# 2.net
KiCad netlist of a schematic drawn in Altium Designer
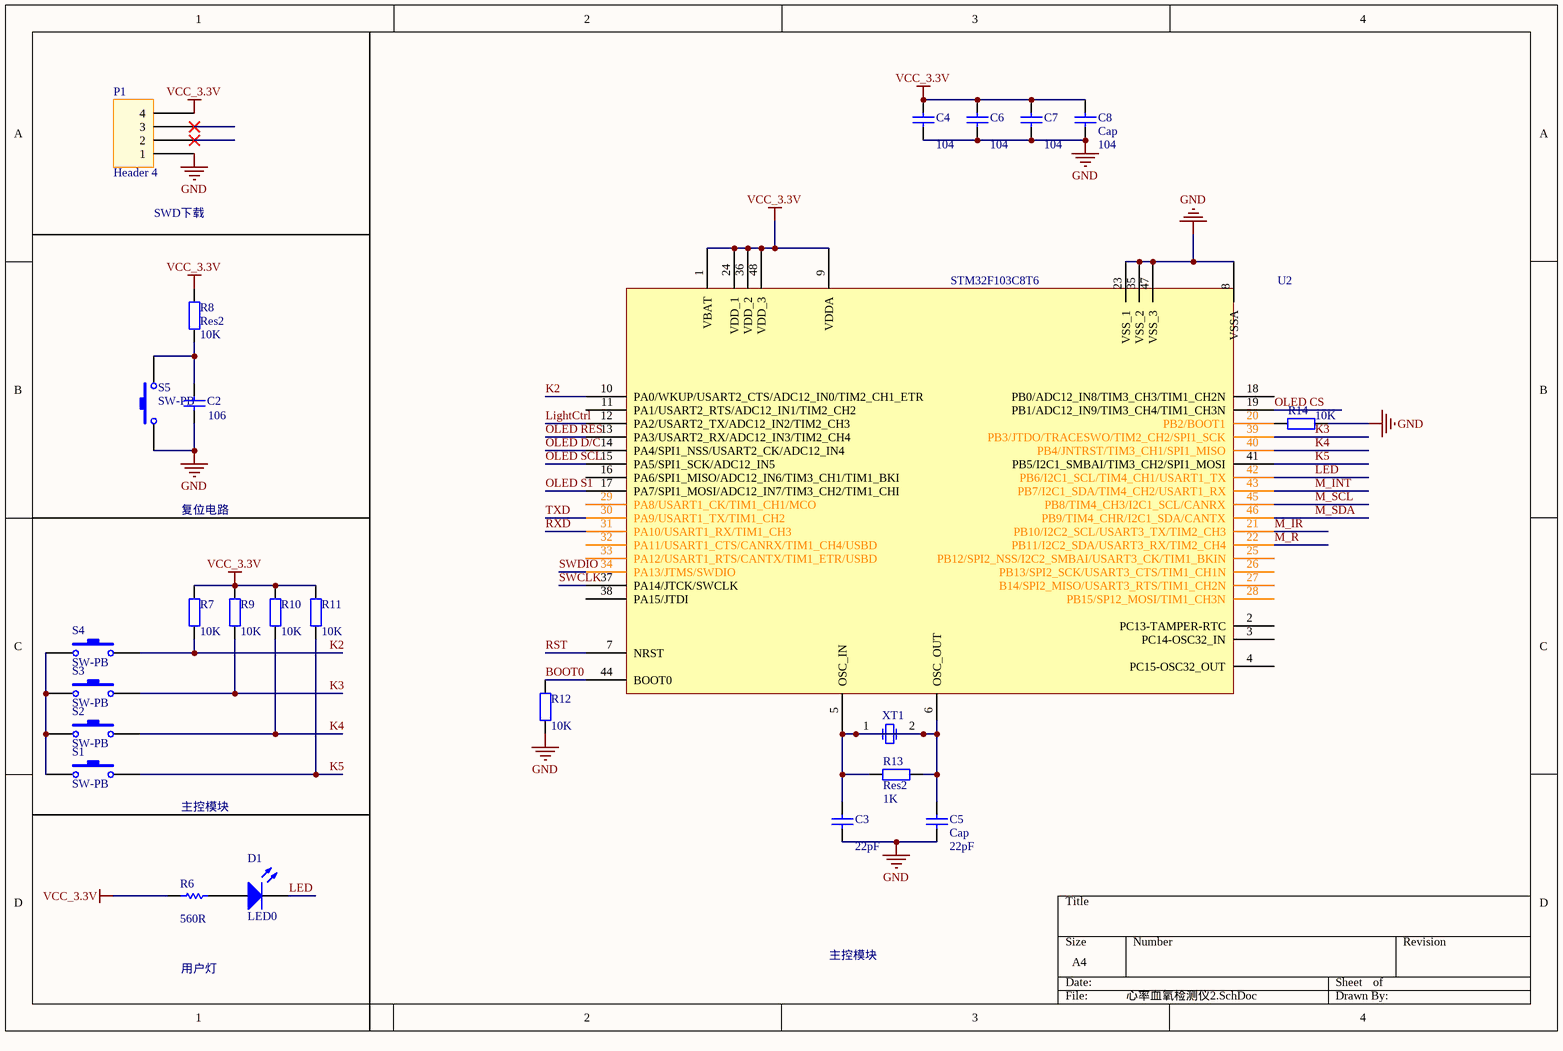
[diagram p0: 心率血氧检测仪2.SchDoc]

(export (version "E")
  (design (tool "Eeschema 10.0.6"))
  (components
    (comp (ref "C2")
      (value "106")
      (footprint "0805C")
      (description "Capacitor")
      (fields (field (name "Comment") "Cap") (field (name "PUBLISHER") "Altium Limited"))
      (libsource (lib "Miscellaneous Devices") (part "Cap"))
    )
    (comp (ref "C3")
      (value "22pF")
      (footprint "0805C")
      (description "Capacitor")
      (fields (field (name "Comment") "Cap") (field (name "PUBLISHER") "Altium Limited"))
      (libsource (lib "Miscellaneous Devices") (part "Cap"))
    )
    (comp (ref "C4")
      (value "104")
      (footprint "0805C")
      (description "Capacitor")
      (fields (field (name "Comment") "Cap") (field (name "PUBLISHER") "Altium Limited"))
      (libsource (lib "Miscellaneous Devices") (part "Cap"))
    )
    (comp (ref "C5")
      (value "Cap")
      (footprint "0805C")
      (description "Capacitor")
      (fields (field (name "ALTIUM_VALUE") "22pF") (field (name "PUBLISHER") "Altium Limited"))
      (libsource (lib "Miscellaneous Devices") (part "Cap"))
    )
    (comp (ref "C6")
      (value "104")
      (footprint "0805C")
      (description "Capacitor")
      (fields (field (name "Comment") "Cap") (field (name "PUBLISHER") "Altium Limited"))
      (libsource (lib "Miscellaneous Devices") (part "Cap"))
    )
    (comp (ref "C7")
      (value "104")
      (footprint "0805C")
      (description "Capacitor")
      (fields (field (name "Comment") "Cap") (field (name "PUBLISHER") "Altium Limited"))
      (libsource (lib "Miscellaneous Devices") (part "Cap"))
    )
    (comp (ref "C8")
      (value "Cap")
      (footprint "0805C")
      (description "Capacitor")
      (fields (field (name "ALTIUM_VALUE") "104") (field (name "PUBLISHER") "Altium Limited"))
      (libsource (lib "Miscellaneous Devices") (part "Cap"))
    )
    (comp (ref "D1")
      (value "LED0")
      (footprint "LED_0805")
      (description "Typical INFRARED GaAs LED")
      (fields (field (name "PUBLISHER") "Altium Limited"))
      (libsource (lib "Miscellaneous Devices") (part "LED0"))
    )
    (comp (ref "P1") (value "Header 4") (footprint "HDR1X4") (libsource (lib "心率血氧") (part "Header 4")))
    (comp (ref "R6")
      (value "560R")
      (footprint "心率血氧2PcbLib1:电阻0805")
      (description "Semiconductor Resistor")
      (fields (field (name "Comment") "Res Semi") (field (name "PUBLISHER") "Altium Limited"))
      (libsource (lib "Miscellaneous Devices") (part "Res Semi"))
    )
    (comp (ref "R7")
      (value "10K")
      (footprint "0805")
      (description "Resistor")
      (fields (field (name "Comment") "Res2") (field (name "PUBLISHER") "Altium Limited"))
      (libsource (lib "Miscellaneous Devices") (part "Res2"))
    )
    (comp (ref "R8")
      (value "Res2")
      (footprint "0805")
      (description "Resistor")
      (fields (field (name "ALTIUM_VALUE") "10K") (field (name "PUBLISHER") "Altium Limited"))
      (libsource (lib "Miscellaneous Devices") (part "Res2"))
    )
    (comp (ref "R9")
      (value "10K")
      (footprint "0805")
      (description "Resistor")
      (fields (field (name "Comment") "Res2") (field (name "PUBLISHER") "Altium Limited"))
      (libsource (lib "Miscellaneous Devices") (part "Res2"))
    )
    (comp (ref "R10")
      (value "10K")
      (footprint "0805")
      (description "Resistor")
      (fields (field (name "Comment") "Res2") (field (name "PUBLISHER") "Altium Limited"))
      (libsource (lib "Miscellaneous Devices") (part "Res2"))
    )
    (comp (ref "R11")
      (value "10K")
      (footprint "0805")
      (description "Resistor")
      (fields (field (name "Comment") "Res2") (field (name "PUBLISHER") "Altium Limited"))
      (libsource (lib "Miscellaneous Devices") (part "Res2"))
    )
    (comp (ref "R12")
      (value "10K")
      (footprint "0805")
      (description "Resistor")
      (fields (field (name "Comment") "Res2") (field (name "PUBLISHER") "Altium Limited"))
      (libsource (lib "Miscellaneous Devices") (part "Res2"))
    )
    (comp (ref "R13")
      (value "Res2")
      (footprint "0805")
      (description "Resistor")
      (fields (field (name "ALTIUM_VALUE") "1K") (field (name "PUBLISHER") "Altium Limited"))
      (libsource (lib "") (part "Res2_1"))
    )
    (comp (ref "R14")
      (value "10K")
      (footprint "0805")
      (description "Resistor")
      (fields (field (name "Comment") "Res2") (field (name "PUBLISHER") "Altium Limited"))
      (libsource (lib "") (part "Res2_1"))
    )
    (comp (ref "S1")
      (value "SW-PB")
      (footprint "2脚按键")
      (description "Switch")
      (fields (field (name "PUBLISHER") "Altium Limited"))
      (libsource (lib "Miscellaneous Devices") (part "SW-PB"))
    )
    (comp (ref "S2")
      (value "SW-PB")
      (footprint "2脚按键")
      (description "Switch")
      (fields (field (name "PUBLISHER") "Altium Limited"))
      (libsource (lib "Miscellaneous Devices") (part "SW-PB"))
    )
    (comp (ref "S3")
      (value "SW-PB")
      (footprint "2脚按键")
      (description "Switch")
      (fields (field (name "PUBLISHER") "Altium Limited"))
      (libsource (lib "Miscellaneous Devices") (part "SW-PB"))
    )
    (comp (ref "S4")
      (value "SW-PB")
      (footprint "2脚按键")
      (description "Switch")
      (fields (field (name "PUBLISHER") "Altium Limited"))
      (libsource (lib "Miscellaneous Devices") (part "SW-PB"))
    )
    (comp (ref "S5")
      (value "SW-PB")
      (footprint "2脚按键")
      (description "Switch")
      (fields (field (name "PUBLISHER") "Altium Limited"))
      (libsource (lib "Miscellaneous Devices") (part "SW-PB"))
    )
    (comp (ref "U2")
      (value "STM32F103C8T6")
      (footprint "LQFP48")
      (libsource (lib "心率血氧") (part "STM32F103C8T6"))
    )
    (comp (ref "XT1")
      (value "XTAL")
      (footprint "HC-49S")
      (description "Crystal Oscillator")
      (fields (field (name "PUBLISHER") "Altium Limited"))
      (libsource (lib "Miscellaneous Devices") (part "XTAL"))
    )
  )
  (nets
    (net (code "1") (name "/BOOT0") (class "Default")
      (node (ref "R12") (pin "2") (pinfunction "2_2") (pintype "passive"))
      (node (ref "U2") (pin "44") (pinfunction "BOOT0_44") (pintype "passive"))
    )
    (net (code "2") (name "/K2") (class "Default")
      (node (ref "R7") (pin "1") (pinfunction "1_1") (pintype "passive"))
      (node (ref "S4") (pin "2") (pinfunction "2_2") (pintype "passive"))
      (node (ref "U2") (pin "10") (pinfunction "PA0/WKUP/USART2_CTS/ADC12_IN0/TIM2_CH1_ETR_10") (pintype "passive"))
    )
    (net (code "3") (name "/K3") (class "Default")
      (node (ref "R9") (pin "1") (pinfunction "1_1") (pintype "passive"))
      (node (ref "S3") (pin "2") (pinfunction "2_2") (pintype "passive"))
      (node (ref "U2") (pin "39") (pinfunction "PB3/JTDO/TRACESWO/TIM2_CH2/SPI1_SCK_39") (pintype "passive"))
    )
    (net (code "4") (name "/K4") (class "Default")
      (node (ref "R10") (pin "1") (pinfunction "1_1") (pintype "passive"))
      (node (ref "S2") (pin "2") (pinfunction "2_2") (pintype "passive"))
      (node (ref "U2") (pin "40") (pinfunction "PB4/JNTRST/TIM3_CH1/SPI1_MISO_40") (pintype "passive"))
    )
    (net (code "5") (name "/K5") (class "Default")
      (node (ref "R11") (pin "1") (pinfunction "1_1") (pintype "passive"))
      (node (ref "S1") (pin "2") (pinfunction "2_2") (pintype "passive"))
      (node (ref "U2") (pin "41") (pinfunction "PB5/I2C1_SMBAI/TIM3_CH2/SPI1_MOSI_41") (pintype "passive"))
    )
    (net (code "6") (name "/LED") (class "Default")
      (node (ref "D1") (pin "2") (pinfunction "K_2") (pintype "passive"))
      (node (ref "U2") (pin "42") (pinfunction "PB6/I2C1_SCL/TIM4_CH1/USART1_TX_42") (pintype "passive"))
    )
    (net (code "7") (name "/LightCtrl") (class "Default")
      (node (ref "U2") (pin "12") (pinfunction "PA2/USART2_TX/ADC12_IN2/TIM2_CH3_12") (pintype "passive"))
    )
    (net (code "8") (name "/M_INT") (class "Default")
      (node (ref "U2") (pin "43") (pinfunction "PB7/I2C1_SDA/TIM4_CH2/USART1_RX_43") (pintype "passive"))
    )
    (net (code "9") (name "/M_IR") (class "Default")
      (node (ref "U2") (pin "21") (pinfunction "PB10/I2C2_SCL/USART3_TX/TIM2_CH3_21") (pintype "passive"))
    )
    (net (code "10") (name "/M_R") (class "Default")
      (node (ref "U2") (pin "22") (pinfunction "PB11/I2C2_SDA/USART3_RX/TIM2_CH4_22") (pintype "passive"))
    )
    (net (code "11") (name "/M_SCL") (class "Default")
      (node (ref "U2") (pin "45") (pinfunction "PB8/TIM4_CH3/I2C1_SCL/CANRX_45") (pintype "passive"))
    )
    (net (code "12") (name "/M_SDA") (class "Default")
      (node (ref "U2") (pin "46") (pinfunction "PB9/TIM4_CHR/I2C1_SDA/CANTX_46") (pintype "passive"))
    )
    (net (code "13") (name "/OLED CS") (class "Default")
      (node (ref "U2") (pin "19") (pinfunction "PB1/ADC12_IN9/TIM3_CH4/TIM1_CH3N_19") (pintype "passive"))
    )
    (net (code "14") (name "/OLED D{slash}C") (class "Default")
      (node (ref "U2") (pin "14") (pinfunction "PA4/SPI1_NSS/USART2_CK/ADC12_IN4_14") (pintype "passive"))
    )
    (net (code "15") (name "/OLED RES") (class "Default")
      (node (ref "U2") (pin "13") (pinfunction "PA3/USART2_RX/ADC12_IN3/TIM2_CH4_13") (pintype "passive"))
    )
    (net (code "16") (name "/OLED S1") (class "Default")
      (node (ref "U2") (pin "17") (pinfunction "PA7/SPI1_MOSI/ADC12_IN7/TIM3_CH2/TIM1_CHI_17") (pintype "passive"))
    )
    (net (code "17") (name "/OLED SCL") (class "Default")
      (node (ref "U2") (pin "15") (pinfunction "PA5/SPI1_SCK/ADC12_IN5_15") (pintype "passive"))
    )
    (net (code "18") (name "/RST") (class "Default")
      (node (ref "U2") (pin "7") (pinfunction "NRST_7") (pintype "passive"))
    )
    (net (code "19") (name "/RXD") (class "Default")
      (node (ref "U2") (pin "31") (pinfunction "PA10/USART1_RX/TIM1_CH3_31") (pintype "passive"))
    )
    (net (code "20") (name "/SWCLK") (class "Default")
      (node (ref "U2") (pin "37") (pinfunction "PA14/JTCK/SWCLK_37") (pintype "passive"))
    )
    (net (code "21") (name "/SWDIO") (class "Default")
      (node (ref "U2") (pin "34") (pinfunction "PA13/JTMS/SWDIO_34") (pintype "passive"))
    )
    (net (code "22") (name "/TXD") (class "Default")
      (node (ref "U2") (pin "30") (pinfunction "PA9/USART1_TX/TIM1_CH2_30") (pintype "passive"))
    )
    (net (code "23") (name "GND") (class "Default")
      (node (ref "C2") (pin "1") (pinfunction "1_1") (pintype "passive"))
      (node (ref "C3") (pin "1") (pinfunction "1_1") (pintype "passive"))
      (node (ref "C4") (pin "1") (pinfunction "1_1") (pintype "passive"))
      (node (ref "C5") (pin "1") (pinfunction "1_1") (pintype "passive"))
      (node (ref "C6") (pin "1") (pinfunction "1_1") (pintype "passive"))
      (node (ref "C7") (pin "1") (pinfunction "1_1") (pintype "passive"))
      (node (ref "C8") (pin "1") (pinfunction "1_1") (pintype "passive"))
      (node (ref "P1") (pin "1") (pinfunction "1_1") (pintype "passive"))
      (node (ref "R12") (pin "1") (pinfunction "1_1") (pintype "passive"))
      (node (ref "R14") (pin "2") (pinfunction "2_2") (pintype "passive"))
      (node (ref "S5") (pin "1") (pinfunction "1_1") (pintype "passive"))
      (node (ref "U2") (pin "23") (pinfunction "VSS_1_23") (pintype "passive"))
      (node (ref "U2") (pin "35") (pinfunction "VSS_2_35") (pintype "passive"))
      (node (ref "U2") (pin "47") (pinfunction "VSS_3_47") (pintype "passive"))
      (node (ref "U2") (pin "8") (pinfunction "VSSA_8") (pintype "passive"))
    )
    (net (code "24") (name "Net-(C2-Pad2)") (class "Default")
      (node (ref "C2") (pin "2") (pinfunction "2_2") (pintype "passive"))
      (node (ref "R8") (pin "1") (pinfunction "1_1") (pintype "passive"))
      (node (ref "S5") (pin "2") (pinfunction "2_2") (pintype "passive"))
    )
    (net (code "25") (name "Net-(D1-A)") (class "Default")
      (node (ref "D1") (pin "1") (pinfunction "A_1") (pintype "passive"))
      (node (ref "R6") (pin "2") (pinfunction "2_2") (pintype "passive"))
    )
    (net (code "26") (name "Net-(S1-Pad1)") (class "Default")
      (node (ref "S1") (pin "1") (pinfunction "1_1") (pintype "passive"))
      (node (ref "S2") (pin "1") (pinfunction "1_1") (pintype "passive"))
      (node (ref "S3") (pin "1") (pinfunction "1_1") (pintype "passive"))
      (node (ref "S4") (pin "1") (pinfunction "1_1") (pintype "passive"))
    )
    (net (code "27") (name "Net-(U2-OSC_IN)") (class "Default")
      (node (ref "C3") (pin "2") (pinfunction "2_2") (pintype "passive"))
      (node (ref "C5") (pin "2") (pinfunction "2_2") (pintype "passive"))
      (node (ref "R13") (pin "1") (pinfunction "1_1") (pintype "passive"))
      (node (ref "R13") (pin "2") (pinfunction "2_2") (pintype "passive"))
      (node (ref "U2") (pin "5") (pinfunction "OSC_IN_5") (pintype "passive"))
      (node (ref "U2") (pin "6") (pinfunction "OSC_OUT_6") (pintype "passive"))
      (node (ref "XT1") (pin "1") (pinfunction "OSC1_1") (pintype "passive"))
      (node (ref "XT1") (pin "2") (pinfunction "OSC2_2") (pintype "passive"))
    )
    (net (code "28") (name "Net-(U2-PB2{slash}BOOT1)") (class "Default")
      (node (ref "R14") (pin "1") (pinfunction "1_1") (pintype "passive"))
      (node (ref "U2") (pin "20") (pinfunction "PB2/BOOT1_20") (pintype "passive"))
    )
    (net (code "29") (name "VCC_3.3V") (class "Default")
      (node (ref "C4") (pin "2") (pinfunction "2_2") (pintype "passive"))
      (node (ref "C6") (pin "2") (pinfunction "2_2") (pintype "passive"))
      (node (ref "C7") (pin "2") (pinfunction "2_2") (pintype "passive"))
      (node (ref "C8") (pin "2") (pinfunction "2_2") (pintype "passive"))
      (node (ref "P1") (pin "4") (pinfunction "4_4") (pintype "passive"))
      (node (ref "R10") (pin "2") (pinfunction "2_2") (pintype "passive"))
      (node (ref "R11") (pin "2") (pinfunction "2_2") (pintype "passive"))
      (node (ref "R6") (pin "1") (pinfunction "1_1") (pintype "passive"))
      (node (ref "R7") (pin "2") (pinfunction "2_2") (pintype "passive"))
      (node (ref "R8") (pin "2") (pinfunction "2_2") (pintype "passive"))
      (node (ref "R9") (pin "2") (pinfunction "2_2") (pintype "passive"))
      (node (ref "U2") (pin "1") (pinfunction "VBAT_1") (pintype "passive"))
      (node (ref "U2") (pin "24") (pinfunction "VDD_1_24") (pintype "passive"))
      (node (ref "U2") (pin "36") (pinfunction "VDD_2_36") (pintype "passive"))
      (node (ref "U2") (pin "48") (pinfunction "VDD_3_48") (pintype "passive"))
      (node (ref "U2") (pin "9") (pinfunction "VDDA_9") (pintype "passive"))
    )
    (net (code "30") (name "unconnected-(P1-Pad2)") (class "Default")
      (node (ref "P1") (pin "2") (pinfunction "2_2") (pintype "passive+no_connect"))
    )
    (net (code "31") (name "unconnected-(P1-Pad3)") (class "Default")
      (node (ref "P1") (pin "3") (pinfunction "3_3") (pintype "passive+no_connect"))
    )
    (net (code "32") (name "unconnected-(U2-B14{slash}SPI2_MISO{slash}USART3_RTS{slash}TIM1_CH2N-Pad27)") (class "Default")
      (node (ref "U2") (pin "27") (pinfunction "B14/SPI2_MISO/USART3_RTS/TIM1_CH2N_27") (pintype "passive"))
    )
    (net (code "33") (name "unconnected-(U2-PA1{slash}USART2_RTS{slash}ADC12_IN1{slash}TIM2_CH2-Pad11)") (class "Default")
      (node (ref "U2") (pin "11") (pinfunction "PA1/USART2_RTS/ADC12_IN1/TIM2_CH2_11") (pintype "passive"))
    )
    (net (code "34") (name "unconnected-(U2-PA6{slash}SPI1_MISO{slash}ADC12_IN6{slash}TIM3_CH1{slash}TIM1_BKI-Pad16)") (class "Default")
      (node (ref "U2") (pin "16") (pinfunction "PA6/SPI1_MISO/ADC12_IN6/TIM3_CH1/TIM1_BKI_16") (pintype "passive"))
    )
    (net (code "35") (name "unconnected-(U2-PA8{slash}USART1_CK{slash}TIM1_CH1{slash}MCO-Pad29)") (class "Default")
      (node (ref "U2") (pin "29") (pinfunction "PA8/USART1_CK/TIM1_CH1/MCO_29") (pintype "passive"))
    )
    (net (code "36") (name "unconnected-(U2-PA11{slash}USART1_CTS{slash}CANRX{slash}TIM1_CH4{slash}USBD-Pad32)") (class "Default")
      (node (ref "U2") (pin "32") (pinfunction "PA11/USART1_CTS/CANRX/TIM1_CH4/USBD_32") (pintype "passive"))
    )
    (net (code "37") (name "unconnected-(U2-PA12{slash}USART1_RTS{slash}CANTX{slash}TIM1_ETR{slash}USBD-Pad33)") (class "Default")
      (node (ref "U2") (pin "33") (pinfunction "PA12/USART1_RTS/CANTX/TIM1_ETR/USBD_33") (pintype "passive"))
    )
    (net (code "38") (name "unconnected-(U2-PA15{slash}JTDI-Pad38)") (class "Default")
      (node (ref "U2") (pin "38") (pinfunction "PA15/JTDI_38") (pintype "passive"))
    )
    (net (code "39") (name "unconnected-(U2-PB0{slash}ADC12_IN8{slash}TIM3_CH3{slash}TIM1_CH2N-Pad18)") (class "Default")
      (node (ref "U2") (pin "18") (pinfunction "PB0/ADC12_IN8/TIM3_CH3/TIM1_CH2N_18") (pintype "passive"))
    )
    (net (code "40") (name "unconnected-(U2-PB12{slash}SPI2_NSS{slash}I2C2_SMBAI{slash}USART3_CK{slash}TIM1_BKIN-Pad25)") (class "Default")
      (node (ref "U2") (pin "25") (pinfunction "PB12/SPI2_NSS/I2C2_SMBAI/USART3_CK/TIM1_BKIN_25") (pintype "passive"))
    )
    (net (code "41") (name "unconnected-(U2-PB13{slash}SPI2_SCK{slash}USART3_CTS{slash}TIM1_CH1N-Pad26)") (class "Default")
      (node (ref "U2") (pin "26") (pinfunction "PB13/SPI2_SCK/USART3_CTS/TIM1_CH1N_26") (pintype "passive"))
    )
    (net (code "42") (name "unconnected-(U2-PB15{slash}SP12_MOSI{slash}TIM1_CH3N-Pad28)") (class "Default")
      (node (ref "U2") (pin "28") (pinfunction "PB15/SP12_MOSI/TIM1_CH3N_28") (pintype "passive"))
    )
    (net (code "43") (name "unconnected-(U2-PC13-TAMPER-RTC-Pad2)") (class "Default")
      (node (ref "U2") (pin "2") (pinfunction "PC13-TAMPER-RTC_2") (pintype "passive"))
    )
    (net (code "44") (name "unconnected-(U2-PC14-OSC32_IN-Pad3)") (class "Default")
      (node (ref "U2") (pin "3") (pinfunction "PC14-OSC32_IN_3") (pintype "passive"))
    )
    (net (code "45") (name "unconnected-(U2-PC15-OSC32_OUT-Pad4)") (class "Default")
      (node (ref "U2") (pin "4") (pinfunction "PC15-OSC32_OUT_4") (pintype "passive"))
    )
  )
)
